# 01_-_SiPM_Carrier.net
KiCad netlist of a schematic drawn in Altium Designer
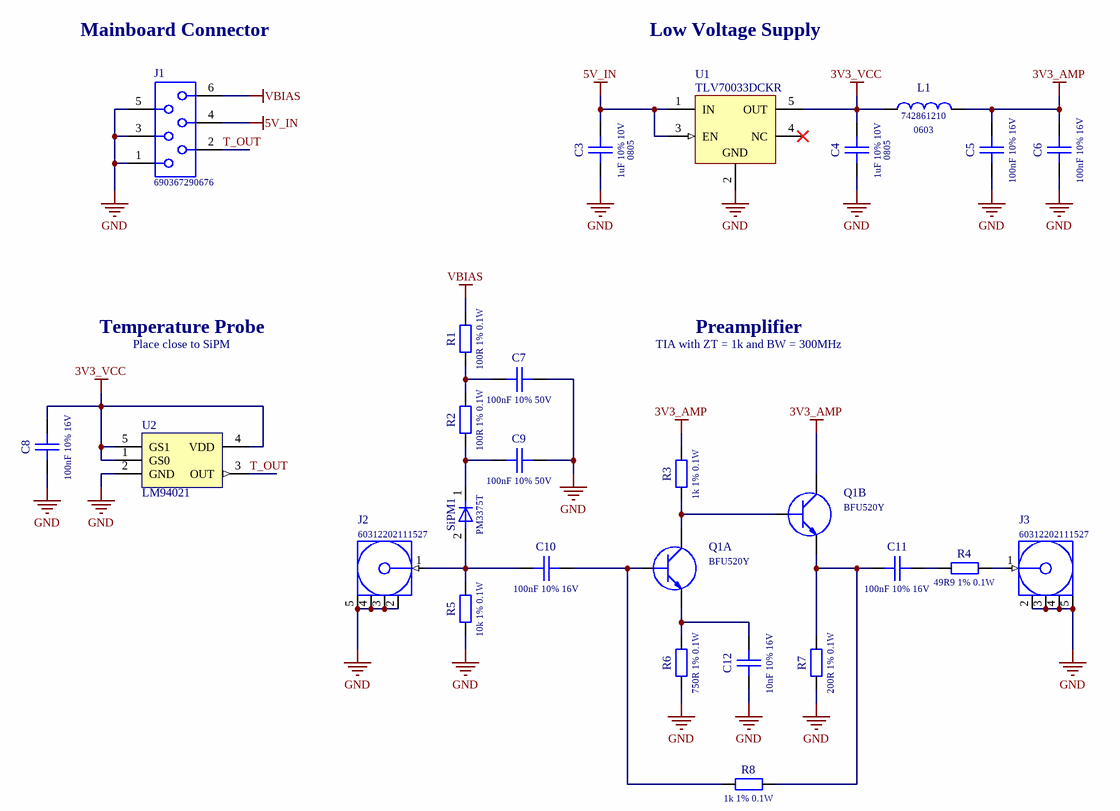
[diagram p0: [01] - SiPM Carrier.SchDoc]

(export (version "E")
  (design (tool "Eeschema 10.0.6"))
  (components
    (comp (ref "C3")
      (value "1uF 10% 10V")
      (footprint "0805_CAP")
      (description "Simple generic capacitor.")
      (fields (field (name "PACKAGEREFERENCE") "0805"))
      (libsource (lib "CustomComponents") (part "Capacitor"))
    )
    (comp (ref "C4")
      (value "1uF 10% 10V")
      (footprint "0805_CAP")
      (description "Simple generic capacitor.")
      (fields (field (name "PACKAGEREFERENCE") "0805"))
      (libsource (lib "CustomComponents") (part "Capacitor"))
    )
    (comp (ref "C5")
      (value "100nF 10% 16V")
      (footprint "0603_CAP")
      (description "Simple generic capacitor.")
      (libsource (lib "CustomComponents") (part "Capacitor"))
    )
    (comp (ref "C6")
      (value "100nF 10% 16V")
      (footprint "0603_CAP")
      (description "Simple generic capacitor.")
      (libsource (lib "CustomComponents") (part "Capacitor"))
    )
    (comp (ref "C7")
      (value "100nF 10% 50V")
      (footprint "0603_CAP")
      (description "Simple generic capacitor.")
      (libsource (lib "CustomComponents") (part "Capacitor"))
    )
    (comp (ref "C8")
      (value "100nF 10% 16V")
      (footprint "0603_CAP")
      (description "Simple generic capacitor.")
      (libsource (lib "CustomComponents") (part "Capacitor"))
    )
    (comp (ref "C9")
      (value "100nF 10% 50V")
      (footprint "0603_CAP")
      (description "Simple generic capacitor.")
      (libsource (lib "CustomComponents") (part "Capacitor"))
    )
    (comp (ref "C10")
      (value "100nF 10% 16V")
      (footprint "0603_CAP")
      (description "Simple generic capacitor.")
      (libsource (lib "CustomComponents") (part "Capacitor"))
    )
    (comp (ref "C11")
      (value "100nF 10% 16V")
      (footprint "0603_CAP")
      (description "Simple generic capacitor.")
      (libsource (lib "CustomComponents") (part "Capacitor"))
    )
    (comp (ref "C12")
      (value "10nF 10% 16V")
      (footprint "0603_CAP")
      (description "Simple generic capacitor.")
      (libsource (lib "CustomComponents") (part "Capacitor"))
    )
    (comp (ref "J1")
      (value "690367290676")
      (footprint "690367290676")
      (description "WR-MM MiniModule Connector, Female, SMT, Vertical, pitch 2.54mm, 6pins")
      (fields (field (name "PUBLISHER") "Wurth Elektronik"))
      (libsource (lib "WR-MM") (part "690367290676"))
    )
    (comp (ref "J2")
      (value "60312202111527")
      (footprint "60312202111527")
      (description "WR-SMA PCB End Launch Jack Round Post for 1.6mm PCB, SMT, Straight")
      (fields (field (name "PUBLISHER") "Wurth Elektronik"))
      (libsource (lib "WR-SMA") (part "60312202111527"))
    )
    (comp (ref "J3")
      (value "60312202111527")
      (footprint "60312202111527")
      (description "WR-SMA PCB End Launch Jack Round Post for 1.6mm PCB, SMT, Straight")
      (fields (field (name "PUBLISHER") "Wurth Elektronik"))
      (libsource (lib "WR-SMA") (part "60312202111527"))
    )
    (comp (ref "L1")
      (value "742861210")
      (footprint "0603_RES")
      (description "Simple generic inductor.")
      (fields (field (name "PARTNUMBER") "XXX") (field (name "PACKAGEREFERENCE") "0603"))
      (libsource (lib "CustomComponents") (part "Inductor"))
    )
    (comp (ref "Q1")
      (value "BFU520Y")
      (footprint "SOT363-6")
      (description "Dual NPN wideband silicon RF transistor.")
      (libsource (lib "CustomComponents") (part "BFU520Y"))
    )
    (comp (ref "R1")
      (value "100R 1% 0.1W")
      (footprint "0603_RES")
      (description "Simple generic resistor.")
      (libsource (lib "CustomComponents") (part "Resistor"))
    )
    (comp (ref "R2")
      (value "100R 1% 0.1W")
      (footprint "0603_RES")
      (description "Simple generic resistor.")
      (libsource (lib "CustomComponents") (part "Resistor"))
    )
    (comp (ref "R3")
      (value "1k 1% 0.1W")
      (footprint "0603_RES")
      (description "Simple generic resistor.")
      (libsource (lib "CustomComponents") (part "Resistor"))
    )
    (comp (ref "R4")
      (value "49R9 1% 0.1W")
      (footprint "0603_RES")
      (description "Simple generic resistor.")
      (libsource (lib "CustomComponents") (part "Resistor"))
    )
    (comp (ref "R5")
      (value "10k 1% 0.1W")
      (footprint "0603_RES")
      (description "Simple generic resistor.")
      (libsource (lib "CustomComponents") (part "Resistor"))
    )
    (comp (ref "R6")
      (value "750R 1% 0.1W")
      (footprint "0603_RES")
      (description "Simple generic resistor.")
      (libsource (lib "CustomComponents") (part "Resistor"))
    )
    (comp (ref "R7")
      (value "200R 1% 0.1W")
      (footprint "0603_RES")
      (description "Simple generic resistor.")
      (libsource (lib "CustomComponents") (part "Resistor"))
    )
    (comp (ref "R8")
      (value "1k 1% 0.1W")
      (footprint "0603_RES")
      (description "Simple generic resistor.")
      (libsource (lib "CustomComponents") (part "Resistor"))
    )
    (comp (ref "SiPM1")
      (value "PM3375T")
      (footprint "PM3375T_SMD")
      (description "Silicon Photomultiplier, 3x3mm2 - 75um type - trench - SMD housing")
      (libsource (lib "CustomComponents") (part "PM3375T"))
    )
    (comp (ref "U1")
      (value "TLV70033DCKR")
      (footprint "TI-DCK5_V")
      (fields (field (name "MANUFACTURER") "Texas Instruments"))
      (libsource (lib "TI Power Management Linear Regulator Single Channel LDO") (part "TLV70033DCKR"))
    )
    (comp (ref "U2")
      (value "LM94021")
      (footprint "SC70")
      (description "Multi-Gain Analog Temperature Sensor.")
      (fields (field (name "MANUFACTURER") "Texas Instruments") (field (name "PARTNUMBER") "LM94021BIMG"))
      (libsource (lib "CustomComponents") (part "LM94021"))
    )
  )
  (nets
    (net (code "1") (name "/T_OUT") (class "Default")
      (node (ref "J1") (pin "2") (pinfunction "2_2") (pintype "passive"))
      (node (ref "U2") (pin "3") (pinfunction "OUT_3") (pintype "output"))
    )
    (net (code "2") (name "3V3_AMP") (class "Default")
      (node (ref "C5") (pin "2") (pinfunction "2_2") (pintype "passive"))
      (node (ref "C6") (pin "2") (pinfunction "2_2") (pintype "passive"))
      (node (ref "L1") (pin "2") (pinfunction "2_2") (pintype "passive"))
      (node (ref "Q1") (pin "3") (pinfunction "C_3") (pintype "passive"))
      (node (ref "R3") (pin "1") (pinfunction "1_1") (pintype "passive"))
    )
    (net (code "3") (name "3V3_VCC") (class "Default")
      (node (ref "C4") (pin "2") (pinfunction "2_2") (pintype "passive"))
      (node (ref "C8") (pin "2") (pinfunction "2_2") (pintype "passive"))
      (node (ref "L1") (pin "1") (pinfunction "1_1") (pintype "passive"))
      (node (ref "U1") (pin "5") (pinfunction "OUT_5") (pintype "power_in"))
      (node (ref "U2") (pin "1") (pinfunction "GS0_1") (pintype "passive"))
      (node (ref "U2") (pin "4") (pinfunction "VDD_4") (pintype "power_in"))
      (node (ref "U2") (pin "5") (pinfunction "GS1_5") (pintype "passive"))
    )
    (net (code "4") (name "5V_IN") (class "Default")
      (node (ref "C3") (pin "2") (pinfunction "2_2") (pintype "passive"))
      (node (ref "J1") (pin "4") (pinfunction "4_4") (pintype "passive"))
      (node (ref "U1") (pin "1") (pinfunction "IN_1") (pintype "power_in"))
      (node (ref "U1") (pin "3") (pinfunction "EN_3") (pintype "input"))
    )
    (net (code "5") (name "GND") (class "Default")
      (node (ref "C12") (pin "1") (pinfunction "1_1") (pintype "passive"))
      (node (ref "C3") (pin "1") (pinfunction "1_1") (pintype "passive"))
      (node (ref "C4") (pin "1") (pinfunction "1_1") (pintype "passive"))
      (node (ref "C5") (pin "1") (pinfunction "1_1") (pintype "passive"))
      (node (ref "C6") (pin "1") (pinfunction "1_1") (pintype "passive"))
      (node (ref "C7") (pin "2") (pinfunction "2_2") (pintype "passive"))
      (node (ref "C8") (pin "1") (pinfunction "1_1") (pintype "passive"))
      (node (ref "C9") (pin "2") (pinfunction "2_2") (pintype "passive"))
      (node (ref "J1") (pin "1") (pinfunction "1_1") (pintype "passive"))
      (node (ref "J1") (pin "3") (pinfunction "3_3") (pintype "passive"))
      (node (ref "J1") (pin "5") (pinfunction "5_5") (pintype "passive"))
      (node (ref "J2") (pin "2") (pinfunction "GND_2") (pintype "power_in"))
      (node (ref "J2") (pin "3") (pinfunction "GND_3") (pintype "power_in"))
      (node (ref "J2") (pin "4") (pinfunction "GND_4") (pintype "power_in"))
      (node (ref "J2") (pin "5") (pinfunction "GND_5") (pintype "power_in"))
      (node (ref "J3") (pin "2") (pinfunction "GND_2") (pintype "power_in"))
      (node (ref "J3") (pin "3") (pinfunction "GND_3") (pintype "power_in"))
      (node (ref "J3") (pin "4") (pinfunction "GND_4") (pintype "power_in"))
      (node (ref "J3") (pin "5") (pinfunction "GND_5") (pintype "power_in"))
      (node (ref "R5") (pin "2") (pinfunction "2_2") (pintype "passive"))
      (node (ref "R6") (pin "2") (pinfunction "2_2") (pintype "passive"))
      (node (ref "R7") (pin "2") (pinfunction "2_2") (pintype "passive"))
      (node (ref "U1") (pin "2") (pinfunction "GND_2") (pintype "power_in"))
      (node (ref "U2") (pin "2") (pinfunction "GND_2") (pintype "power_in"))
    )
    (net (code "6") (name "Net-(C7-Pad1)") (class "Default")
      (node (ref "C7") (pin "1") (pinfunction "1_1") (pintype "passive"))
      (node (ref "R1") (pin "2") (pinfunction "2_2") (pintype "passive"))
      (node (ref "R2") (pin "1") (pinfunction "1_1") (pintype "passive"))
    )
    (net (code "7") (name "Net-(C11-Pad2)") (class "Default")
      (node (ref "C11") (pin "2") (pinfunction "2_2") (pintype "passive"))
      (node (ref "R4") (pin "2") (pinfunction "2_2") (pintype "passive"))
    )
    (net (code "8") (name "Net-(J2-Signal)") (class "Default")
      (node (ref "C10") (pin "1") (pinfunction "1_1") (pintype "passive"))
      (node (ref "J2") (pin "1") (pinfunction "Signal_1") (pintype "input"))
      (node (ref "R5") (pin "1") (pinfunction "1_1") (pintype "passive"))
      (node (ref "SiPM1") (pin "2") (pinfunction "A_2") (pintype "passive"))
    )
    (net (code "9") (name "Net-(J3-Signal)") (class "Default")
      (node (ref "J3") (pin "1") (pinfunction "Signal_1") (pintype "input"))
      (node (ref "R4") (pin "1") (pinfunction "1_1") (pintype "passive"))
    )
    (net (code "10") (name "Net-(Q1A-B)") (class "Default")
      (node (ref "C10") (pin "2") (pinfunction "2_2") (pintype "passive"))
      (node (ref "Q1") (pin "1") (pinfunction "B_1") (pintype "passive"))
      (node (ref "R8") (pin "2") (pinfunction "2_2") (pintype "passive"))
    )
    (net (code "11") (name "Net-(Q1A-C)") (class "Default")
      (node (ref "Q1") (pin "4") (pinfunction "B_4") (pintype "passive"))
      (node (ref "Q1") (pin "6") (pinfunction "C_6") (pintype "passive"))
      (node (ref "R3") (pin "2") (pinfunction "2_2") (pintype "passive"))
    )
    (net (code "12") (name "Net-(Q1A-E)") (class "Default")
      (node (ref "C12") (pin "2") (pinfunction "2_2") (pintype "passive"))
      (node (ref "Q1") (pin "2") (pinfunction "E_2") (pintype "passive"))
      (node (ref "R6") (pin "1") (pinfunction "1_1") (pintype "passive"))
    )
    (net (code "13") (name "Net-(Q1B-E)") (class "Default")
      (node (ref "C11") (pin "1") (pinfunction "1_1") (pintype "passive"))
      (node (ref "Q1") (pin "5") (pinfunction "E_5") (pintype "passive"))
      (node (ref "R7") (pin "1") (pinfunction "1_1") (pintype "passive"))
      (node (ref "R8") (pin "1") (pinfunction "1_1") (pintype "passive"))
    )
    (net (code "14") (name "Net-(SiPM1-C)") (class "Default")
      (node (ref "C9") (pin "1") (pinfunction "1_1") (pintype "passive"))
      (node (ref "R2") (pin "2") (pinfunction "2_2") (pintype "passive"))
      (node (ref "SiPM1") (pin "1") (pinfunction "C_1") (pintype "passive"))
    )
    (net (code "15") (name "VBIAS") (class "Default")
      (node (ref "J1") (pin "6") (pinfunction "6_6") (pintype "passive"))
      (node (ref "R1") (pin "1") (pinfunction "1_1") (pintype "passive"))
    )
    (net (code "16") (name "unconnected-(U1-NC-Pad4)") (class "Default")
      (node (ref "U1") (pin "4") (pinfunction "NC_4") (pintype "passive+no_connect"))
    )
  )
)
